# 5VSwitchablePowerOutput.net
KiCad netlist of a schematic drawn in EAGLE
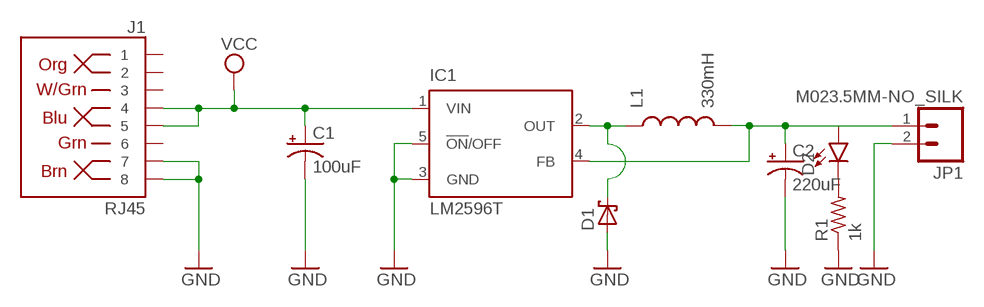
[diagram p0: schematic, sheet 1]

(export (version "E")
  (design (tool "Eeschema 10.0.6"))
  (components
    (comp (ref "C1")
      (value "100uF")
      (footprint "eagle-import:E5-13")
      (libsource (lib "eagle-import") (part "CPOL-USE5-13"))
    )
    (comp (ref "C2")
      (value "220uF")
      (footprint "eagle-import:E3,5-10")
      (libsource (lib "eagle-import") (part "CPOL-USE3.5-10"))
    )
    (comp (ref "D1")
      (value "SCHOTTKY-DIODECB417-15")
      (footprint "eagle-import:CB417-15")
      (libsource (lib "eagle-import") (part "SCHOTTKY-DIODECB417-15"))
    )
    (comp (ref "D2")
      (value "LED5MM")
      (footprint "eagle-import:LED_5MM")
      (libsource (lib "eagle-import") (part "LED5MM"))
    )
    (comp (ref "IC1")
      (value "LM2596T")
      (footprint "eagle-import:T05D")
      (fields (field (name "MPN") "LM2596T-ADJ/LF02"))
      (libsource (lib "eagle-import") (part "LM2596T"))
    )
    (comp (ref "J1")
      (value "RJ45")
      (footprint "eagle-import:RJ45-8")
      (libsource (lib "eagle-import") (part "RJ45-8"))
    )
    (comp (ref "JP1")
      (value "M023.5MM-NO_SILK")
      (footprint "eagle-import:SCREWTERMINAL-3.5MM-2-NS")
      (libsource (lib "eagle-import") (part "M023.5MM-NO_SILK"))
    )
    (comp (ref "L1")
      (value "330mH")
      (footprint "eagle-import:RLB0912")
      (libsource (lib "eagle-import") (part "INDUCTORRLB0912"))
    )
    (comp (ref "R1")
      (value "1k")
      (footprint "eagle-import:0204_7")
      (libsource (lib "eagle-import") (part "R-US_0204/7"))
    )
  )
  (nets
    (net (code "1") (name "GND") (class "Default")
      (node (ref "C1") (pin "-") (pinfunction "-_-") (pintype "passive"))
      (node (ref "C2") (pin "-") (pinfunction "-_-") (pintype "passive"))
      (node (ref "D1") (pin "A") (pinfunction "A_A") (pintype "passive"))
      (node (ref "IC1") (pin "3") (pinfunction "GND_3") (pintype "power_in"))
      (node (ref "IC1") (pin "5") (pinfunction "~{ON}/OFF_5") (pintype "input"))
      (node (ref "J1") (pin "7") (pinfunction "7_7") (pintype "bidirectional"))
      (node (ref "J1") (pin "8") (pinfunction "8_8") (pintype "bidirectional"))
      (node (ref "JP1") (pin "2") (pinfunction "2_2") (pintype "passive"))
      (node (ref "R1") (pin "1") (pinfunction "1_1") (pintype "passive"))
    )
    (net (code "2") (name "Net-(D2-C)") (class "Default")
      (node (ref "D2") (pin "K") (pinfunction "C_K") (pintype "passive"))
      (node (ref "R1") (pin "2") (pinfunction "2_2") (pintype "passive"))
    )
    (net (code "3") (name "Net-(IC1-FB)") (class "Default")
      (node (ref "C2") (pin "+") (pinfunction "+_+") (pintype "passive"))
      (node (ref "D2") (pin "A") (pinfunction "A_A") (pintype "passive"))
      (node (ref "IC1") (pin "4") (pinfunction "FB_4") (pintype "input"))
      (node (ref "JP1") (pin "1") (pinfunction "1_1") (pintype "passive"))
      (node (ref "L1") (pin "2") (pinfunction "2_2") (pintype "passive"))
    )
    (net (code "4") (name "Net-(IC1-OUT)") (class "Default")
      (node (ref "D1") (pin "C") (pinfunction "C_C") (pintype "passive"))
      (node (ref "IC1") (pin "2") (pinfunction "OUT_2") (pintype "output"))
      (node (ref "L1") (pin "1") (pinfunction "1_1") (pintype "passive"))
    )
    (net (code "5") (name "VCC") (class "Default")
      (node (ref "C1") (pin "+") (pinfunction "+_+") (pintype "passive"))
      (node (ref "IC1") (pin "1") (pinfunction "VIN_1") (pintype "input"))
      (node (ref "J1") (pin "4") (pinfunction "4_4") (pintype "bidirectional"))
      (node (ref "J1") (pin "5") (pinfunction "5_5") (pintype "bidirectional"))
    )
    (net (code "6") (name "unconnected-(J1-Pad1)") (class "Default")
      (node (ref "J1") (pin "1") (pinfunction "1_1") (pintype "bidirectional"))
    )
    (net (code "7") (name "unconnected-(J1-Pad2)") (class "Default")
      (node (ref "J1") (pin "2") (pinfunction "2_2") (pintype "bidirectional"))
    )
    (net (code "8") (name "unconnected-(J1-Pad3)") (class "Default")
      (node (ref "J1") (pin "3") (pinfunction "3_3") (pintype "bidirectional"))
    )
    (net (code "9") (name "unconnected-(J1-Pad6)") (class "Default")
      (node (ref "J1") (pin "6") (pinfunction "6_6") (pintype "bidirectional"))
    )
  )
)
